# Mach_do_do_am_Hs1101-_do_nhiet_do_18b20.net
KiCad netlist of a schematic drawn in Altium Designer
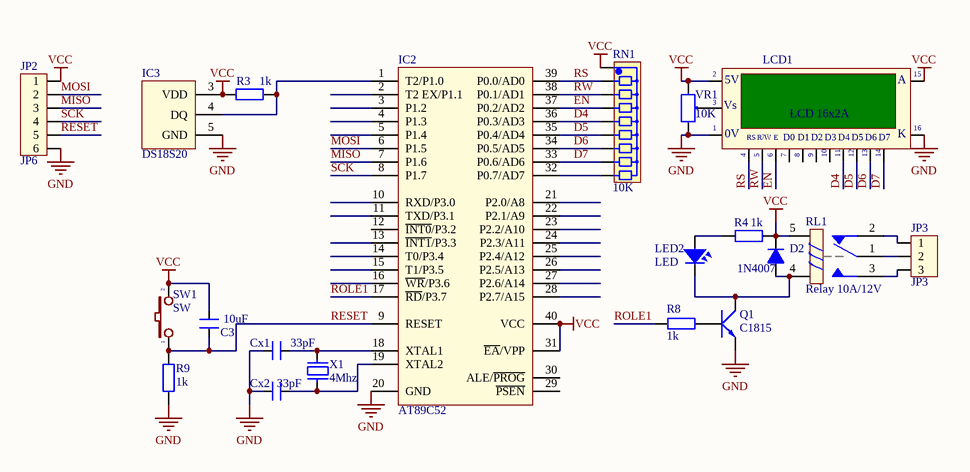
[diagram p0: Mach do do am Hs1101- do nhiet do 18b20.SchDoc]

(export (version "E")
  (design (tool "Eeschema 10.0.6"))
  (components
    (comp (ref "C3")
      (value "10uF")
      (footprint "CN1")
      (description "Cap np  1pF - 472pF")
      (libsource (lib "tungdcn") (part "CN1"))
    )
    (comp (ref "Cx1")
      (value "33pF")
      (footprint "CN1")
      (description "Cremic For Xtal 1pF => 100pF")
      (libsource (lib "tungdcn") (part "CN0"))
    )
    (comp (ref "Cx2")
      (value "33pF")
      (footprint "CN1")
      (description "Cremic For Xtal 1pF => 100pF")
      (libsource (lib "tungdcn") (part "CN0"))
    )
    (comp (ref "D2")
      (value "1N4007")
      (footprint "D1A")
      (description "Diode 1A")
      (libsource (lib "tungdcn") (part "D1A"))
    )
    (comp (ref "IC2")
      (value "AT89C52")
      (footprint "DIP40/W0.6")
      (description "Atmel AT89C52, 8k Byte Flash Memory , 40 Pin")
      (libsource (lib "tungdcn") (part "AT89C52"))
    )
    (comp (ref "IC3")
      (value "DS18S20")
      (footprint "DS18S20")
      (description "High Precision  1-Wire® Digital Thermometer")
      (libsource (lib "tungdcn") (part "DS18S20"))
    )
    (comp (ref "JP2")
      (value "JP6")
      (footprint "CON6")
      (description "Connector 6")
      (libsource (lib "tungdcn") (part "Con6"))
    )
    (comp (ref "JP3")
      (value "JP3")
      (footprint "CON3")
      (description "Connector 3")
      (libsource (lib "tungdcn") (part "Con3"))
    )
    (comp (ref "LCD1")
      (value "LCD 16x2A")
      (footprint "LCD16X2")
      (description "LCD dipslay 16 char, 2 line")
      (libsource (lib "tungdcn") (part "LCD16x2A"))
    )
    (comp (ref "LED2")
      (value "LED")
      (footprint "LED-3")
      (description "LED Single colour Green and Red")
      (libsource (lib "tungdcn") (part "LED"))
    )
    (comp (ref "Q1")
      (value "C1815")
      (footprint "QTO-92")
      (description "NPN 600mW, ECB")
      (libsource (lib "tungdcn") (part "C1815"))
    )
    (comp (ref "R3")
      (value "1k")
      (footprint "R1/4W")
      (description "Resistor 1/4W")
      (libsource (lib "tungdcn") (part "R1/4W"))
    )
    (comp (ref "R4")
      (value "1k")
      (footprint "R1/4W")
      (description "Resistor 1/4W")
      (libsource (lib "tungdcn") (part "R1/4W"))
    )
    (comp (ref "R8")
      (value "1k")
      (footprint "R1/4W")
      (description "Resistor 1/4W")
      (libsource (lib "tungdcn") (part "R1/4W"))
    )
    (comp (ref "R9")
      (value "1k")
      (footprint "R1/4W")
      (description "Resistor 1/4W")
      (libsource (lib "tungdcn") (part "R1/4W"))
    )
    (comp (ref "RL1")
      (value "Relay 10A/12V")
      (footprint "RL_SPDT_10A")
      (description "Relay SPDT,10A - 12VDC 5 Pin")
      (libsource (lib "tungdcn") (part "Relay 1"))
    )
    (comp (ref "RN1")
      (value "10K")
      (footprint "RN8")
      (description "Resistor 8 (Thanh)")
      (libsource (lib "tungdcn") (part "RN8"))
    )
    (comp (ref "SW1")
      (value "SW")
      (footprint "SW2")
      (description "Switch button 2 pin")
      (libsource (lib "tungdcn") (part "SW2"))
    )
    (comp (ref "VR1")
      (value "10K")
      (footprint "VR")
      (description "Var Resistor")
      (libsource (lib "tungdcn") (part "VR"))
    )
    (comp (ref "X1")
      (value "4Mhz")
      (footprint "XT2")
      (description "Crystal For all Crystal 2pin.")
      (libsource (lib "tungdcn") (part "XT2"))
    )
  )
  (nets
    (net (code "1") (name "/D4") (class "Default")
      (node (ref "IC2") (pin "36") (pinfunction "P0.3/AD3_36") (pintype "passive"))
      (node (ref "LCD1") (pin "11") (pinfunction "D4_11") (pintype "passive"))
      (node (ref "RN1") (pin "5") (pinfunction "5_5") (pintype "passive"))
    )
    (net (code "2") (name "/D5") (class "Default")
      (node (ref "IC2") (pin "35") (pinfunction "P0.4/AD4_35") (pintype "passive"))
      (node (ref "LCD1") (pin "12") (pinfunction "D5_12") (pintype "passive"))
      (node (ref "RN1") (pin "6") (pinfunction "6_6") (pintype "passive"))
    )
    (net (code "3") (name "/D6") (class "Default")
      (node (ref "IC2") (pin "34") (pinfunction "P0.5/AD5_34") (pintype "passive"))
      (node (ref "LCD1") (pin "13") (pinfunction "D6_13") (pintype "passive"))
      (node (ref "RN1") (pin "7") (pinfunction "7_7") (pintype "passive"))
    )
    (net (code "4") (name "/D7") (class "Default")
      (node (ref "IC2") (pin "33") (pinfunction "P0.6/AD6_33") (pintype "passive"))
      (node (ref "LCD1") (pin "14") (pinfunction "D7_14") (pintype "passive"))
      (node (ref "RN1") (pin "8") (pinfunction "8_8") (pintype "passive"))
    )
    (net (code "5") (name "/EN") (class "Default")
      (node (ref "IC2") (pin "37") (pinfunction "P0.2/AD2_37") (pintype "passive"))
      (node (ref "LCD1") (pin "6") (pinfunction "~{EN}_6") (pintype "passive"))
      (node (ref "RN1") (pin "4") (pinfunction "4_4") (pintype "passive"))
    )
    (net (code "6") (name "/MISO") (class "Default")
      (node (ref "IC2") (pin "7") (pinfunction "P1.6_7") (pintype "passive"))
      (node (ref "JP2") (pin "3") (pinfunction "3_3") (pintype "passive"))
    )
    (net (code "7") (name "/MOSI") (class "Default")
      (node (ref "IC2") (pin "6") (pinfunction "P1.5_6") (pintype "passive"))
      (node (ref "JP2") (pin "2") (pinfunction "2_2") (pintype "passive"))
    )
    (net (code "8") (name "/RESET") (class "Default")
      (node (ref "C3") (pin "2") (pinfunction "2_2") (pintype "passive"))
      (node (ref "IC2") (pin "9") (pinfunction "RESET_9") (pintype "passive"))
      (node (ref "JP2") (pin "5") (pinfunction "5_5") (pintype "passive"))
      (node (ref "R9") (pin "1") (pinfunction "1_1") (pintype "passive"))
      (node (ref "SW1") (pin "1") (pinfunction "1_1") (pintype "passive"))
    )
    (net (code "9") (name "/ROLE1") (class "Default")
      (node (ref "IC2") (pin "17") (pinfunction "~{RD}/P3.7_17") (pintype "passive"))
      (node (ref "R8") (pin "1") (pinfunction "1_1") (pintype "passive"))
    )
    (net (code "10") (name "/RS") (class "Default")
      (node (ref "IC2") (pin "39") (pinfunction "P0.0/AD0_39") (pintype "passive"))
      (node (ref "LCD1") (pin "4") (pinfunction "RS_4") (pintype "passive"))
      (node (ref "RN1") (pin "2") (pinfunction "2_2") (pintype "passive"))
    )
    (net (code "11") (name "/RW") (class "Default")
      (node (ref "IC2") (pin "38") (pinfunction "P0.1/AD1_38") (pintype "passive"))
      (node (ref "LCD1") (pin "5") (pinfunction "R/~{W}_5") (pintype "passive"))
      (node (ref "RN1") (pin "3") (pinfunction "3_3") (pintype "passive"))
    )
    (net (code "12") (name "/SCK") (class "Default")
      (node (ref "IC2") (pin "8") (pinfunction "P1.7_8") (pintype "passive"))
      (node (ref "JP2") (pin "4") (pinfunction "4_4") (pintype "passive"))
    )
    (net (code "13") (name "GND") (class "Default")
      (node (ref "Cx1") (pin "2") (pinfunction "2_2") (pintype "passive"))
      (node (ref "Cx2") (pin "2") (pinfunction "2_2") (pintype "passive"))
      (node (ref "IC2") (pin "20") (pinfunction "GND_20") (pintype "open_emitter"))
      (node (ref "IC3") (pin "5") (pinfunction "GND_5") (pintype "passive"))
      (node (ref "JP2") (pin "6") (pinfunction "6_6") (pintype "passive"))
      (node (ref "LCD1") (pin "1") (pinfunction "GND_1") (pintype "passive"))
      (node (ref "LCD1") (pin "16") (pinfunction "K_16") (pintype "passive"))
      (node (ref "Q1") (pin "1") (pinfunction "E_1") (pintype "passive"))
      (node (ref "R9") (pin "2") (pinfunction "2_2") (pintype "passive"))
      (node (ref "VR1") (pin "3") (pinfunction "3_3") (pintype "passive"))
    )
    (net (code "14") (name "Net-(D2-A)") (class "Default")
      (node (ref "D2") (pin "1") (pinfunction "A_1") (pintype "passive"))
      (node (ref "LED2") (pin "2") (pinfunction "2_2") (pintype "passive"))
      (node (ref "Q1") (pin "2") (pinfunction "C_2") (pintype "passive"))
      (node (ref "RL1") (pin "4") (pinfunction "4_4") (pintype "passive"))
    )
    (net (code "15") (name "Net-(IC2-P0.7{slash}AD7)") (class "Default")
      (node (ref "IC2") (pin "32") (pinfunction "P0.7/AD7_32") (pintype "passive"))
      (node (ref "RN1") (pin "9") (pinfunction "9_9") (pintype "passive"))
    )
    (net (code "16") (name "Net-(IC2-T2{slash}P1.0)") (class "Default")
      (node (ref "IC2") (pin "1") (pinfunction "T2/P1.0_1") (pintype "passive"))
      (node (ref "IC3") (pin "4") (pinfunction "DQ_4") (pintype "passive"))
      (node (ref "R3") (pin "2") (pinfunction "2_2") (pintype "passive"))
    )
    (net (code "17") (name "Net-(IC2-XTAL1)") (class "Default")
      (node (ref "Cx1") (pin "1") (pinfunction "1_1") (pintype "passive"))
      (node (ref "IC2") (pin "18") (pinfunction "XTAL1_18") (pintype "passive"))
      (node (ref "X1") (pin "2") (pinfunction "2_2") (pintype "passive"))
    )
    (net (code "18") (name "Net-(IC2-XTAL2)") (class "Default")
      (node (ref "Cx2") (pin "1") (pinfunction "1_1") (pintype "passive"))
      (node (ref "IC2") (pin "19") (pinfunction "XTAL2_19") (pintype "passive"))
      (node (ref "X1") (pin "1") (pinfunction "1_1") (pintype "passive"))
    )
    (net (code "19") (name "Net-(JP3-Pad1)") (class "Default")
      (node (ref "JP3") (pin "1") (pinfunction "1_1") (pintype "passive"))
      (node (ref "RL1") (pin "2") (pinfunction "2_2") (pintype "passive"))
    )
    (net (code "20") (name "Net-(JP3-Pad2)") (class "Default")
      (node (ref "JP3") (pin "2") (pinfunction "2_2") (pintype "passive"))
      (node (ref "RL1") (pin "1") (pinfunction "1_1") (pintype "passive"))
    )
    (net (code "21") (name "Net-(JP3-Pad3)") (class "Default")
      (node (ref "JP3") (pin "3") (pinfunction "3_3") (pintype "passive"))
      (node (ref "RL1") (pin "3") (pinfunction "3_3") (pintype "passive"))
    )
    (net (code "22") (name "Net-(LCD1-VEE)") (class "Default")
      (node (ref "LCD1") (pin "3") (pinfunction "VEE_3") (pintype "passive"))
      (node (ref "VR1") (pin "2") (pinfunction "2_2") (pintype "passive"))
    )
    (net (code "23") (name "Net-(LED2-Pad1)") (class "Default")
      (node (ref "LED2") (pin "1") (pinfunction "1_1") (pintype "passive"))
      (node (ref "R4") (pin "1") (pinfunction "1_1") (pintype "passive"))
    )
    (net (code "24") (name "Net-(Q1-B)") (class "Default")
      (node (ref "Q1") (pin "3") (pinfunction "B_3") (pintype "passive"))
      (node (ref "R8") (pin "2") (pinfunction "2_2") (pintype "passive"))
    )
    (net (code "25") (name "VCC") (class "Default")
      (node (ref "C3") (pin "1") (pinfunction "1_1") (pintype "passive"))
      (node (ref "D2") (pin "2") (pinfunction "K_2") (pintype "passive"))
      (node (ref "IC2") (pin "31") (pinfunction "~{EA}/VPP_31") (pintype "passive"))
      (node (ref "IC2") (pin "40") (pinfunction "VCC_40") (pintype "power_in"))
      (node (ref "IC3") (pin "3") (pinfunction "VDD_3") (pintype "passive"))
      (node (ref "JP2") (pin "1") (pinfunction "1_1") (pintype "passive"))
      (node (ref "LCD1") (pin "15") (pinfunction "A_15") (pintype "passive"))
      (node (ref "LCD1") (pin "2") (pinfunction "VDD_2") (pintype "passive"))
      (node (ref "R3") (pin "1") (pinfunction "1_1") (pintype "passive"))
      (node (ref "R4") (pin "2") (pinfunction "2_2") (pintype "passive"))
      (node (ref "RL1") (pin "5") (pinfunction "5_5") (pintype "passive"))
      (node (ref "RN1") (pin "1") (pinfunction "1_1") (pintype "passive"))
      (node (ref "SW1") (pin "2") (pinfunction "2_2") (pintype "passive"))
      (node (ref "VR1") (pin "1") (pinfunction "1_1") (pintype "passive"))
    )
    (net (code "26") (name "unconnected-(IC2-ALE{slash}~{PROG}-Pad30)") (class "Default")
      (node (ref "IC2") (pin "30") (pinfunction "ALE/~{PROG}_30") (pintype "passive"))
    )
    (net (code "27") (name "unconnected-(IC2-P1.2-Pad3)") (class "Default")
      (node (ref "IC2") (pin "3") (pinfunction "P1.2_3") (pintype "passive"))
    )
    (net (code "28") (name "unconnected-(IC2-P1.3-Pad4)") (class "Default")
      (node (ref "IC2") (pin "4") (pinfunction "P1.3_4") (pintype "passive"))
    )
    (net (code "29") (name "unconnected-(IC2-P1.4-Pad5)") (class "Default")
      (node (ref "IC2") (pin "5") (pinfunction "P1.4_5") (pintype "passive"))
    )
    (net (code "30") (name "unconnected-(IC2-P2.0{slash}A8-Pad21)") (class "Default")
      (node (ref "IC2") (pin "21") (pinfunction "P2.0/A8_21") (pintype "passive"))
    )
    (net (code "31") (name "unconnected-(IC2-P2.1{slash}A9-Pad22)") (class "Default")
      (node (ref "IC2") (pin "22") (pinfunction "P2.1/A9_22") (pintype "passive"))
    )
    (net (code "32") (name "unconnected-(IC2-P2.2{slash}A10-Pad23)") (class "Default")
      (node (ref "IC2") (pin "23") (pinfunction "P2.2/A10_23") (pintype "passive"))
    )
    (net (code "33") (name "unconnected-(IC2-P2.3{slash}A11-Pad24)") (class "Default")
      (node (ref "IC2") (pin "24") (pinfunction "P2.3/A11_24") (pintype "passive"))
    )
    (net (code "34") (name "unconnected-(IC2-P2.4{slash}A12-Pad25)") (class "Default")
      (node (ref "IC2") (pin "25") (pinfunction "P2.4/A12_25") (pintype "passive"))
    )
    (net (code "35") (name "unconnected-(IC2-P2.5{slash}A13-Pad26)") (class "Default")
      (node (ref "IC2") (pin "26") (pinfunction "P2.5/A13_26") (pintype "passive"))
    )
    (net (code "36") (name "unconnected-(IC2-P2.6{slash}A14-Pad27)") (class "Default")
      (node (ref "IC2") (pin "27") (pinfunction "P2.6/A14_27") (pintype "passive"))
    )
    (net (code "37") (name "unconnected-(IC2-P2.7{slash}A15-Pad28)") (class "Default")
      (node (ref "IC2") (pin "28") (pinfunction "P2.7/A15_28") (pintype "passive"))
    )
    (net (code "38") (name "unconnected-(IC2-RXD{slash}P3.0-Pad10)") (class "Default")
      (node (ref "IC2") (pin "10") (pinfunction "RXD/P3.0_10") (pintype "passive"))
    )
    (net (code "39") (name "unconnected-(IC2-T0{slash}P3.4-Pad14)") (class "Default")
      (node (ref "IC2") (pin "14") (pinfunction "T0/P3.4_14") (pintype "passive"))
    )
    (net (code "40") (name "unconnected-(IC2-T1{slash}P3.5-Pad15)") (class "Default")
      (node (ref "IC2") (pin "15") (pinfunction "T1/P3.5_15") (pintype "passive"))
    )
    (net (code "41") (name "unconnected-(IC2-T2_EX{slash}P1.1-Pad2)") (class "Default")
      (node (ref "IC2") (pin "2") (pinfunction "T2_EX/P1.1_2") (pintype "passive"))
    )
    (net (code "42") (name "unconnected-(IC2-TXD{slash}P3.1-Pad11)") (class "Default")
      (node (ref "IC2") (pin "11") (pinfunction "TXD/P3.1_11") (pintype "passive"))
    )
    (net (code "43") (name "unconnected-(IC2-~{INT0}{slash}P3.2-Pad12)") (class "Default")
      (node (ref "IC2") (pin "12") (pinfunction "~{INT0}/P3.2_12") (pintype "passive"))
    )
    (net (code "44") (name "unconnected-(IC2-~{INT1}{slash}P3.3-Pad13)") (class "Default")
      (node (ref "IC2") (pin "13") (pinfunction "~{INT1}/P3.3_13") (pintype "passive"))
    )
    (net (code "45") (name "unconnected-(IC2-~{PSEN}-Pad29)") (class "Default")
      (node (ref "IC2") (pin "29") (pinfunction "~{PSEN}_29") (pintype "passive"))
    )
    (net (code "46") (name "unconnected-(IC2-~{WR}{slash}P3.6-Pad16)") (class "Default")
      (node (ref "IC2") (pin "16") (pinfunction "~{WR}/P3.6_16") (pintype "passive"))
    )
    (net (code "47") (name "unconnected-(LCD1-D0-Pad7)") (class "Default")
      (node (ref "LCD1") (pin "7") (pinfunction "D0_7") (pintype "passive"))
    )
    (net (code "48") (name "unconnected-(LCD1-D1-Pad8)") (class "Default")
      (node (ref "LCD1") (pin "8") (pinfunction "D1_8") (pintype "passive"))
    )
    (net (code "49") (name "unconnected-(LCD1-D2-Pad9)") (class "Default")
      (node (ref "LCD1") (pin "9") (pinfunction "D2_9") (pintype "passive"))
    )
    (net (code "50") (name "unconnected-(LCD1-D3-Pad10)") (class "Default")
      (node (ref "LCD1") (pin "10") (pinfunction "D3_10") (pintype "passive"))
    )
  )
)
